# power_supply.net
KiCad netlist of a schematic drawn in EAGLE
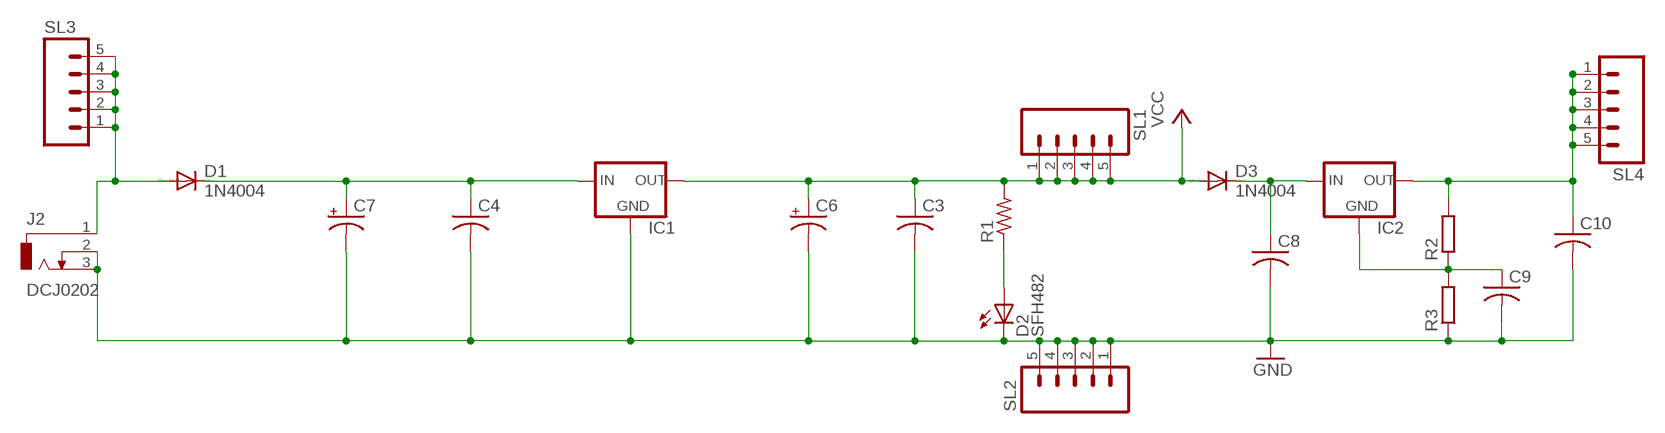
[diagram p0: schematic, sheet 1]

(export (version "E")
  (design (tool "Eeschema 10.0.6"))
  (components
    (comp (ref "C3")
      (value "C-US025-025X050")
      (footprint "eagle-import:C025-025X050")
      (libsource (lib "eagle-import") (part "C-US025-025X050"))
    )
    (comp (ref "C4")
      (value "C-US025-025X050")
      (footprint "eagle-import:C025-025X050")
      (libsource (lib "eagle-import") (part "C-US025-025X050"))
    )
    (comp (ref "C6")
      (value "CPOL-USE3.5-10")
      (footprint "eagle-import:E3,5-10")
      (libsource (lib "eagle-import") (part "CPOL-USE3.5-10"))
    )
    (comp (ref "C7")
      (value "CPOL-USE3.5-10")
      (footprint "eagle-import:E3,5-10")
      (libsource (lib "eagle-import") (part "CPOL-USE3.5-10"))
    )
    (comp (ref "C8")
      (value "C-US025-025X050")
      (footprint "eagle-import:C025-025X050")
      (libsource (lib "eagle-import") (part "C-US025-025X050"))
    )
    (comp (ref "C9")
      (value "C-US025-025X050")
      (footprint "eagle-import:C025-025X050")
      (libsource (lib "eagle-import") (part "C-US025-025X050"))
    )
    (comp (ref "C10")
      (value "C-US025-025X050")
      (footprint "eagle-import:C025-025X050")
      (libsource (lib "eagle-import") (part "C-US025-025X050"))
    )
    (comp (ref "D1")
      (value "1N4004")
      (footprint "eagle-import:DO41-10")
      (libsource (lib "eagle-import") (part "1N4004"))
    )
    (comp (ref "D2")
      (value "SFH482")
      (footprint "eagle-import:SFH482")
      (libsource (lib "eagle-import") (part "SFH482"))
    )
    (comp (ref "D3")
      (value "1N4004")
      (footprint "eagle-import:DO41-10")
      (libsource (lib "eagle-import") (part "1N4004"))
    )
    (comp (ref "IC1")
      (value "78MXXS")
      (footprint "eagle-import:78MXXS")
      (libsource (lib "eagle-import") (part "78MXXS"))
    )
    (comp (ref "IC2")
      (value "78MXXS")
      (footprint "eagle-import:78MXXS")
      (libsource (lib "eagle-import") (part "78MXXS"))
    )
    (comp (ref "J2")
      (value "DCJ0202")
      (footprint "eagle-import:DCJ0202")
      (libsource (lib "eagle-import") (part "DCJ0202"))
    )
    (comp (ref "R1")
      (value "R-US_0204/7")
      (footprint "eagle-import:0204_7")
      (libsource (lib "eagle-import") (part "R-US_0204/7"))
    )
    (comp (ref "R2")
      (value "R-EU_0204/7")
      (footprint "eagle-import:0204_7")
      (libsource (lib "eagle-import") (part "R-EU_0204/7"))
    )
    (comp (ref "R3")
      (value "R-EU_0204/7")
      (footprint "eagle-import:0204_7")
      (libsource (lib "eagle-import") (part "R-EU_0204/7"))
    )
    (comp (ref "SL1")
      (value "M05")
      (footprint "eagle-import:05P")
      (libsource (lib "eagle-import") (part "M05"))
    )
    (comp (ref "SL2")
      (value "M05")
      (footprint "eagle-import:05P")
      (libsource (lib "eagle-import") (part "M05"))
    )
    (comp (ref "SL3")
      (value "M05")
      (footprint "eagle-import:05P")
      (libsource (lib "eagle-import") (part "M05"))
    )
    (comp (ref "SL4")
      (value "M05")
      (footprint "eagle-import:05P")
      (libsource (lib "eagle-import") (part "M05"))
    )
  )
  (nets
    (net (code "1") (name "GND") (class "Default")
      (node (ref "C10") (pin "2") (pinfunction "2_2") (pintype "passive"))
      (node (ref "C3") (pin "2") (pinfunction "2_2") (pintype "passive"))
      (node (ref "C4") (pin "2") (pinfunction "2_2") (pintype "passive"))
      (node (ref "C6") (pin "-") (pinfunction "-_-") (pintype "passive"))
      (node (ref "C7") (pin "-") (pinfunction "-_-") (pintype "passive"))
      (node (ref "C8") (pin "2") (pinfunction "2_2") (pintype "passive"))
      (node (ref "C9") (pin "2") (pinfunction "2_2") (pintype "passive"))
      (node (ref "D2") (pin "K") (pinfunction "C_K") (pintype "passive"))
      (node (ref "IC1") (pin "GND") (pinfunction "GND_GND") (pintype "input"))
      (node (ref "J2") (pin "2") (pinfunction "2_2") (pintype "passive"))
      (node (ref "J2") (pin "3") (pinfunction "3_3") (pintype "passive"))
      (node (ref "R3") (pin "1") (pinfunction "1_1") (pintype "passive"))
      (node (ref "SL2") (pin "1") (pinfunction "1_1") (pintype "passive"))
      (node (ref "SL2") (pin "2") (pinfunction "2_2") (pintype "passive"))
      (node (ref "SL2") (pin "3") (pinfunction "3_3") (pintype "passive"))
      (node (ref "SL2") (pin "4") (pinfunction "4_4") (pintype "passive"))
      (node (ref "SL2") (pin "5") (pinfunction "5_5") (pintype "passive"))
    )
    (net (code "2") (name "Net-(C4-Pad1)") (class "Default")
      (node (ref "C4") (pin "1") (pinfunction "1_1") (pintype "passive"))
      (node (ref "C7") (pin "+") (pinfunction "+_+") (pintype "passive"))
      (node (ref "D1") (pin "C") (pinfunction "C_C") (pintype "passive"))
      (node (ref "IC1") (pin "IN") (pinfunction "IN_IN") (pintype "input"))
    )
    (net (code "3") (name "Net-(C8-Pad1)") (class "Default")
      (node (ref "C8") (pin "1") (pinfunction "1_1") (pintype "passive"))
      (node (ref "D3") (pin "C") (pinfunction "C_C") (pintype "passive"))
      (node (ref "IC2") (pin "IN") (pinfunction "IN_IN") (pintype "input"))
    )
    (net (code "4") (name "Net-(C9-Pad1)") (class "Default")
      (node (ref "C9") (pin "1") (pinfunction "1_1") (pintype "passive"))
      (node (ref "IC2") (pin "GND") (pinfunction "GND_GND") (pintype "input"))
      (node (ref "R2") (pin "1") (pinfunction "1_1") (pintype "passive"))
      (node (ref "R3") (pin "2") (pinfunction "2_2") (pintype "passive"))
    )
    (net (code "5") (name "Net-(C10-Pad1)") (class "Default")
      (node (ref "C10") (pin "1") (pinfunction "1_1") (pintype "passive"))
      (node (ref "IC2") (pin "OUT") (pinfunction "OUT_OUT") (pintype "passive"))
      (node (ref "R2") (pin "2") (pinfunction "2_2") (pintype "passive"))
      (node (ref "SL4") (pin "1") (pinfunction "1_1") (pintype "passive"))
      (node (ref "SL4") (pin "2") (pinfunction "2_2") (pintype "passive"))
      (node (ref "SL4") (pin "3") (pinfunction "3_3") (pintype "passive"))
      (node (ref "SL4") (pin "4") (pinfunction "4_4") (pintype "passive"))
      (node (ref "SL4") (pin "5") (pinfunction "5_5") (pintype "passive"))
    )
    (net (code "6") (name "Net-(D1-PadA)") (class "Default")
      (node (ref "D1") (pin "A") (pinfunction "A_A") (pintype "passive"))
      (node (ref "J2") (pin "1") (pinfunction "1_1") (pintype "passive"))
      (node (ref "SL3") (pin "1") (pinfunction "1_1") (pintype "passive"))
      (node (ref "SL3") (pin "2") (pinfunction "2_2") (pintype "passive"))
      (node (ref "SL3") (pin "3") (pinfunction "3_3") (pintype "passive"))
      (node (ref "SL3") (pin "4") (pinfunction "4_4") (pintype "passive"))
      (node (ref "SL3") (pin "5") (pinfunction "5_5") (pintype "passive"))
    )
    (net (code "7") (name "Net-(D2-PadA)") (class "Default")
      (node (ref "D2") (pin "A") (pinfunction "A_A") (pintype "passive"))
      (node (ref "R1") (pin "1") (pinfunction "1_1") (pintype "passive"))
    )
    (net (code "8") (name "VCC") (class "Default")
      (node (ref "C3") (pin "1") (pinfunction "1_1") (pintype "passive"))
      (node (ref "C6") (pin "+") (pinfunction "+_+") (pintype "passive"))
      (node (ref "D3") (pin "A") (pinfunction "A_A") (pintype "passive"))
      (node (ref "IC1") (pin "OUT") (pinfunction "OUT_OUT") (pintype "passive"))
      (node (ref "R1") (pin "2") (pinfunction "2_2") (pintype "passive"))
      (node (ref "SL1") (pin "1") (pinfunction "1_1") (pintype "passive"))
      (node (ref "SL1") (pin "2") (pinfunction "2_2") (pintype "passive"))
      (node (ref "SL1") (pin "3") (pinfunction "3_3") (pintype "passive"))
      (node (ref "SL1") (pin "4") (pinfunction "4_4") (pintype "passive"))
      (node (ref "SL1") (pin "5") (pinfunction "5_5") (pintype "passive"))
    )
  )
)
